# Power_Supply.net
KiCad netlist of a schematic drawn in Altium Designer
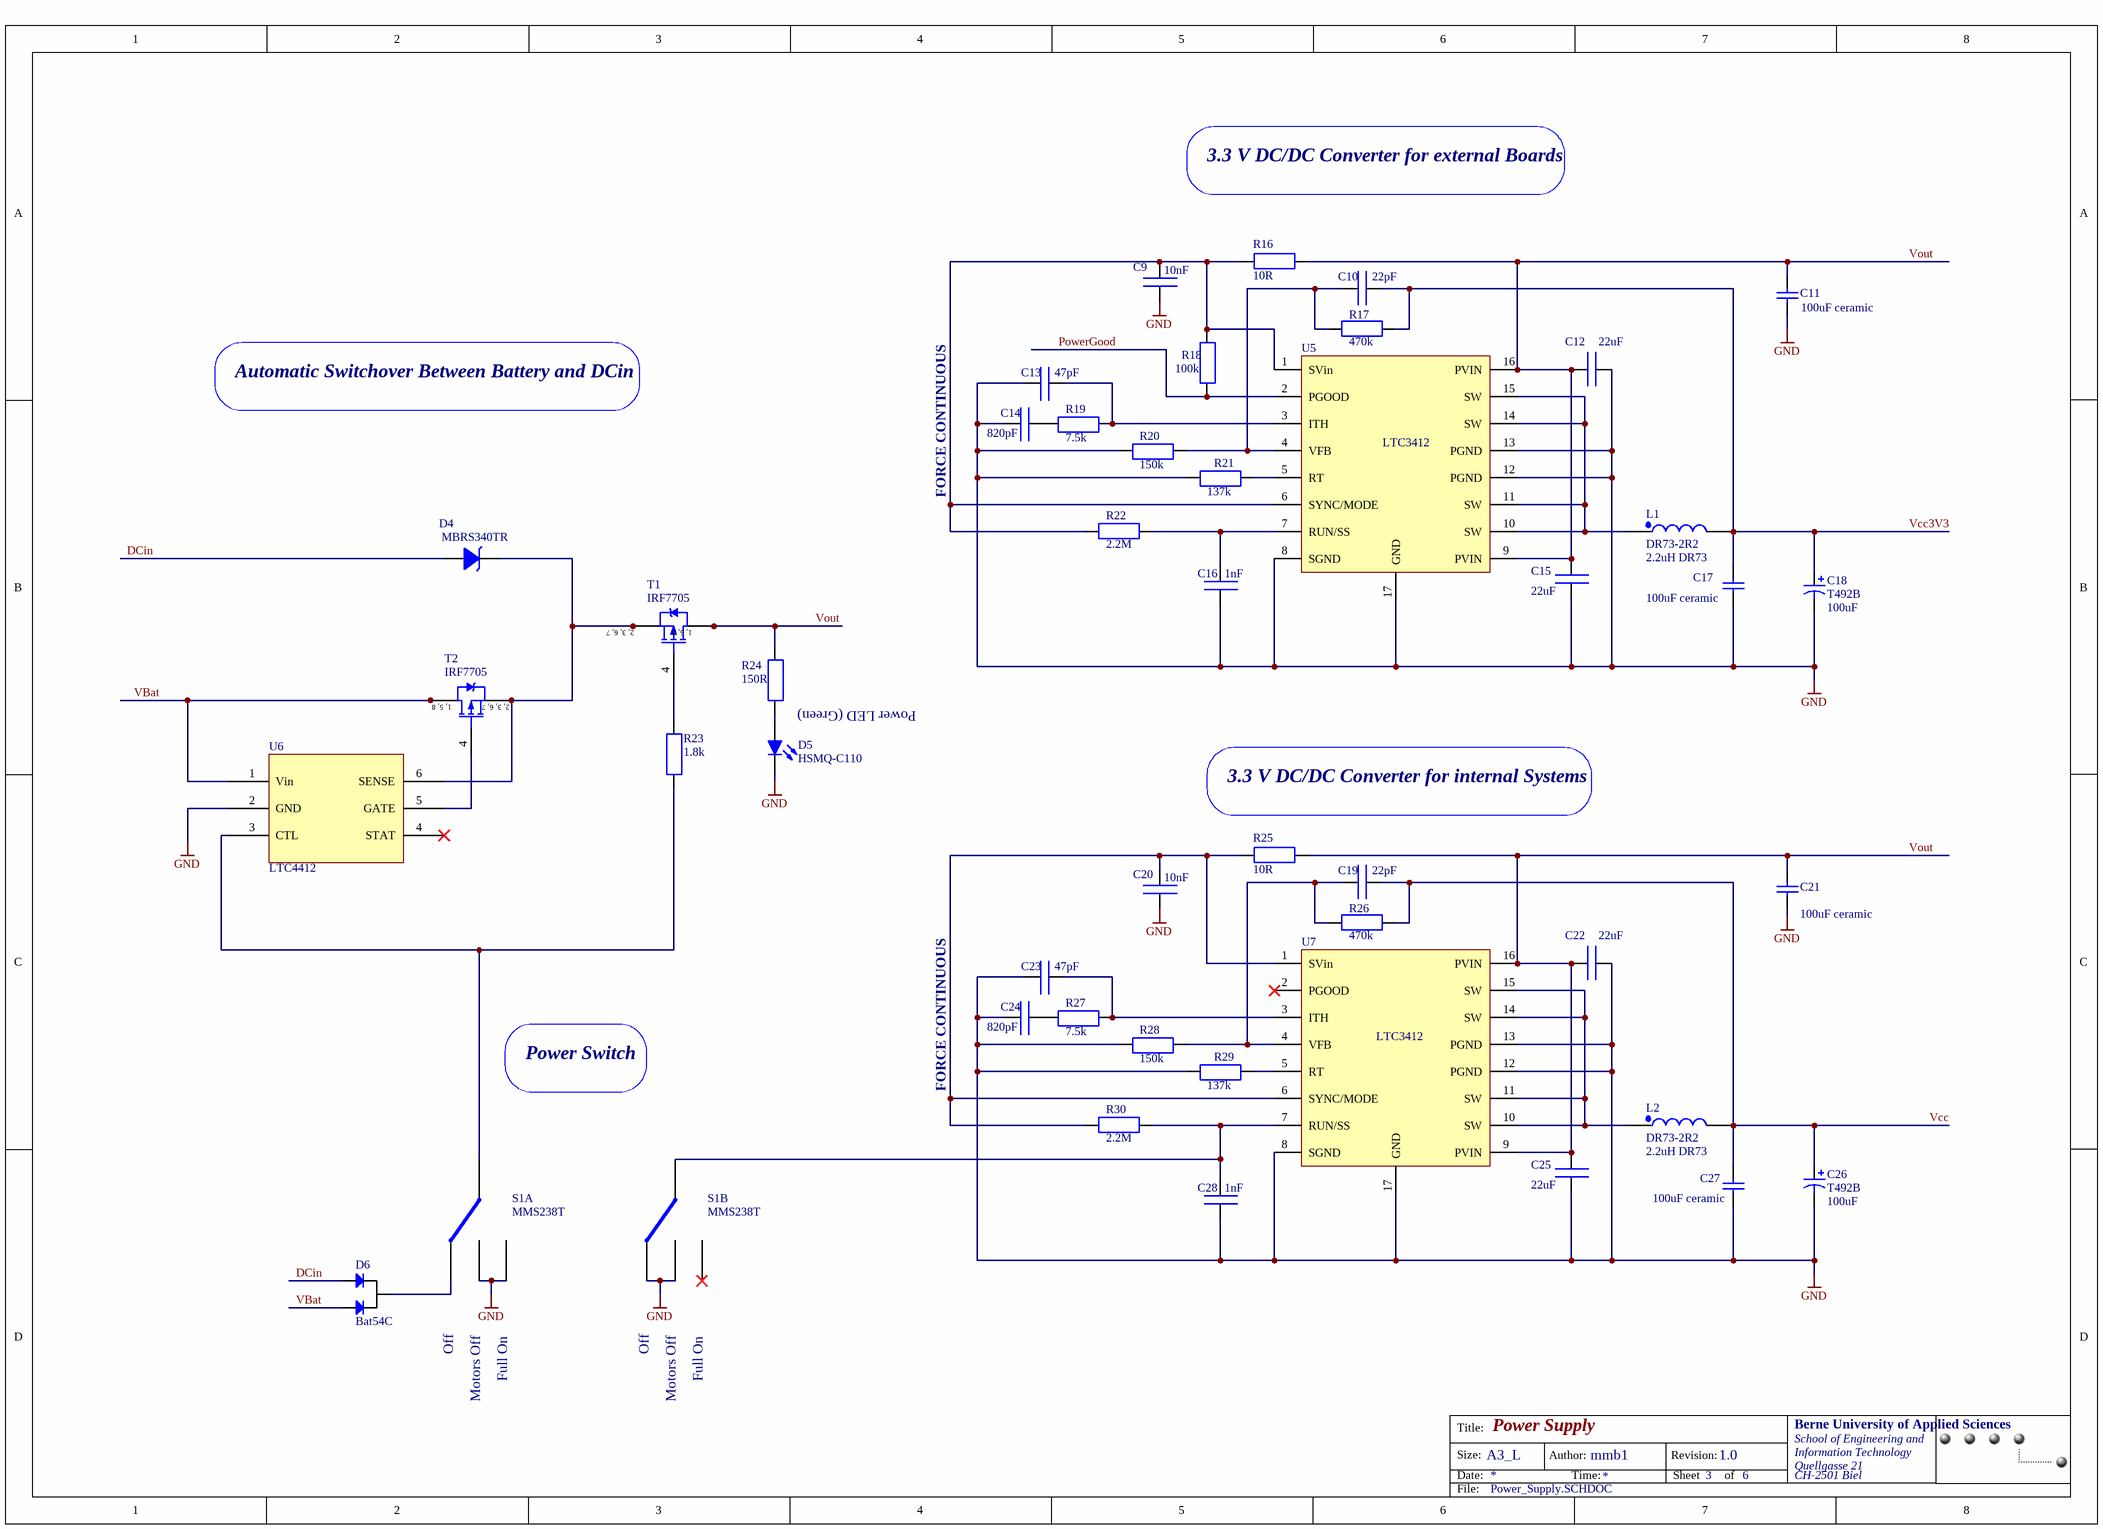
[diagram p0: Power_Supply.SCHDOC]

(export (version "E")
  (design (tool "Eeschema 10.0.6"))
  (components
    (comp (ref "C9")
      (value "10nF")
      (footprint "1608[0603]")
      (description "Capacitor")
      (fields
        (field (name "PART TYPE") "10nF")
        (field (name "MANUFACTURER") "AVX")
        (field (name "PART NUMBER") "06035C103KAT2A")
      )
      (libsource (lib "POWER_SUPPLY") (part "CAP"))
    )
    (comp (ref "C10")
      (value "22pF")
      (footprint "1608[0603]")
      (description "Capacitor")
      (fields
        (field (name "PART TYPE") "22pF")
        (field (name "MANUFACTURER") "Epcos")
        (field (name "PART NUMBER") "B37930K5220J60")
      )
      (libsource (lib "POWER_SUPPLY") (part "CAP"))
    )
    (comp (ref "C11")
      (value "100uF ceramic")
      (footprint "C1210")
      (description "Capacitor (Semiconductor SIM Model)")
      (fields
        (field (name "MANUFACTURER") "Kemet")
        (field (name "PART NUMBER") "C1210C107M9PAC7800")
        (field (name "PUBLISHER") "Altium Limited")
      )
      (libsource (lib "Miscellaneous Devices") (part "Cap Semi"))
    )
    (comp (ref "C12")
      (value "22uF")
      (footprint "C0805")
      (description "Capacitor")
      (fields (field (name "MANUFACTURER") "Kemet") (field (name "PART NUMBER") "C0805C226M9PAC7800"))
      (libsource (lib "POWER_SUPPLY") (part "CAP"))
    )
    (comp (ref "C13")
      (value "47pF")
      (footprint "1608[0603]")
      (description "Capacitor")
      (fields
        (field (name "PART TYPE") "47pF")
        (field (name "MANUFACTURER") "Murata")
        (field (name "PART NUMBER") "GRM1885C1H470JA01D")
      )
      (libsource (lib "POWER_SUPPLY") (part "CAP"))
    )
    (comp (ref "C14")
      (value "820pF")
      (footprint "1608[0603]")
      (description "Capacitor")
      (fields
        (field (name "PART TYPE") "820pF")
        (field (name "MANUFACTURER") "PHYCOMP")
        (field (name "PART NUMBER") "2238 861 15821")
      )
      (libsource (lib "POWER_SUPPLY") (part "CAP"))
    )
    (comp (ref "C15")
      (value "22uF")
      (footprint "C0805")
      (description "Capacitor")
      (fields (field (name "MANUFACTURER") "Kemet") (field (name "PART NUMBER") "C0805C226M9PAC7800"))
      (libsource (lib "POWER_SUPPLY") (part "CAP"))
    )
    (comp (ref "C16")
      (value "1nF")
      (footprint "1608[0603]")
      (description "Capacitor")
      (fields
        (field (name "PART TYPE") "1nF")
        (field (name "MANUFACTURER") "Murata")
        (field (name "PART NUMBER") "GRM188R71H102KA01D")
      )
      (libsource (lib "POWER_SUPPLY") (part "CAP"))
    )
    (comp (ref "C17")
      (value "100uF ceramic")
      (footprint "C1210")
      (description "Capacitor (Semiconductor SIM Model)")
      (fields
        (field (name "MANUFACTURER") "Kemet")
        (field (name "PART NUMBER") "C1210C107M9PAC7800")
        (field (name "PUBLISHER") "Altium Limited")
      )
      (libsource (lib "Miscellaneous Devices") (part "Cap Semi"))
    )
    (comp (ref "C18")
      (value "T492B")
      (footprint "B")
      (description "Solid Tantalum Chip Capacitor, T492 Series - CWR11 Style Per Mil-PRF-55365/8")
      (fields
        (field (name "ALTIUM_VALUE") "100uF")
        (field (name "MANUFACTURER") "AVX")
        (field (name "PART NUMBER") "TCJB107M004R0070")
        (field (name "PUBLISHER") "Altium Limited")
      )
      (libsource (lib "KEMET Chip Capacitor") (part "T492B"))
    )
    (comp (ref "C19")
      (value "22pF")
      (footprint "1608[0603]")
      (description "Capacitor")
      (fields
        (field (name "PART TYPE") "22pF")
        (field (name "MANUFACTURER") "Epcos")
        (field (name "PART NUMBER") "B37930K5220J60")
      )
      (libsource (lib "POWER_SUPPLY") (part "CAP"))
    )
    (comp (ref "C20")
      (value "10nF")
      (footprint "1608[0603]")
      (description "Capacitor")
      (fields
        (field (name "PART TYPE") "10nF")
        (field (name "MANUFACTURER") "AVX")
        (field (name "PART NUMBER") "06035C103KAT2A")
      )
      (libsource (lib "POWER_SUPPLY") (part "CAP"))
    )
    (comp (ref "C21")
      (value "100uF ceramic")
      (footprint "C1210")
      (description "Capacitor (Semiconductor SIM Model)")
      (fields
        (field (name "MANUFACTURER") "Kemet")
        (field (name "PART NUMBER") "C1210C107M9PAC7800")
        (field (name "PUBLISHER") "Altium Limited")
      )
      (libsource (lib "Miscellaneous Devices") (part "Cap Semi"))
    )
    (comp (ref "C22")
      (value "22uF")
      (footprint "C0805")
      (description "Capacitor")
      (fields (field (name "MANUFACTURER") "Kemet") (field (name "PART NUMBER") "C0805C226M9PAC7800"))
      (libsource (lib "POWER_SUPPLY") (part "CAP"))
    )
    (comp (ref "C23")
      (value "47pF")
      (footprint "1608[0603]")
      (description "Capacitor")
      (fields
        (field (name "PART TYPE") "47pF")
        (field (name "MANUFACTURER") "Murata")
        (field (name "PART NUMBER") "GRM1885C1H470JA01D")
      )
      (libsource (lib "POWER_SUPPLY") (part "CAP"))
    )
    (comp (ref "C24")
      (value "820pF")
      (footprint "1608[0603]")
      (description "Capacitor")
      (fields
        (field (name "PART TYPE") "820pF")
        (field (name "MANUFACTURER") "PHYCOMP")
        (field (name "PART NUMBER") "2238 861 15821")
      )
      (libsource (lib "POWER_SUPPLY") (part "CAP"))
    )
    (comp (ref "C25")
      (value "22uF")
      (footprint "C0805")
      (description "Capacitor")
      (fields (field (name "MANUFACTURER") "Kemet") (field (name "PART NUMBER") "C0805C226M9PAC7800"))
      (libsource (lib "POWER_SUPPLY") (part "CAP"))
    )
    (comp (ref "C26")
      (value "T492B")
      (footprint "B")
      (description "Solid Tantalum Chip Capacitor, T492 Series - CWR11 Style Per Mil-PRF-55365/8")
      (fields
        (field (name "ALTIUM_VALUE") "100uF")
        (field (name "MANUFACTURER") "AVX")
        (field (name "PART NUMBER") "TCJB107M004R0070")
        (field (name "PUBLISHER") "Altium Limited")
      )
      (libsource (lib "KEMET Chip Capacitor") (part "T492B"))
    )
    (comp (ref "C27")
      (value "100uF ceramic")
      (footprint "C1210")
      (description "Capacitor (Semiconductor SIM Model)")
      (fields
        (field (name "MANUFACTURER") "Kemet")
        (field (name "PART NUMBER") "C1210C107M9PAC7800")
        (field (name "PUBLISHER") "Altium Limited")
      )
      (libsource (lib "Miscellaneous Devices") (part "Cap Semi"))
    )
    (comp (ref "C28")
      (value "1nF")
      (footprint "1608[0603]")
      (description "Capacitor")
      (fields
        (field (name "PART TYPE") "1nF")
        (field (name "MANUFACTURER") "Murata")
        (field (name "PART NUMBER") "GRM188R71H102KA01D")
      )
      (libsource (lib "POWER_SUPPLY") (part "CAP"))
    )
    (comp (ref "D4")
      (value "MBRS340TR")
      (footprint "MBRS340")
      (fields
        (field (name "MANUFACTURER") "Vishay")
        (field (name "PART NUMBER") "MBRS340TRPBF")
        (field (name "Comment") "Schottky  Power Rectifier")
      )
      (libsource (lib "Power_supply") (part "shottky-mbrs340tr"))
    )
    (comp (ref "D5")
      (value "HSMQ-C110")
      (footprint "HSMC-C110")
      (description "LED")
      (fields (field (name "PART TYPE") "HSMQ-C110") (field (name "MANUFACTURER") "Avago"))
      (libsource (lib "Power_supply") (part "LED-HSM*-C110"))
    )
    (comp (ref "D6")
      (value "Bat54C")
      (footprint "BAT54C")
      (fields
        (field (name "PART TYPE") "Bat54C")
        (field (name "MANUFACTURER") "ST")
        (field (name "PART NUMBER") "BAT54CFILM")
      )
      (libsource (lib "Power_supply") (part "BAT54C"))
    )
    (comp (ref "L1")
      (value "2.2uH DR73")
      (footprint "B82472G4222M")
      (description "DR Series Coils from Coiltronics")
      (fields
        (field (name "PART TYPE") "DR73-2R2")
        (field (name "MANUFACTURER") "Cooper Bussmann")
        (field (name "PART NUMBER") "DR73-2R2")
      )
      (libsource (lib "Power_supply") (part "COIL-DR-SERIE"))
    )
    (comp (ref "L2")
      (value "2.2uH DR73")
      (footprint "B82472G4222M")
      (description "DR Series Coils from Coiltronics")
      (fields
        (field (name "PART TYPE") "DR73-2R2")
        (field (name "MANUFACTURER") "Cooper Bussmann")
        (field (name "PART NUMBER") "DR73-2R2")
      )
      (libsource (lib "Power_supply") (part "COIL-DR-SERIE"))
    )
    (comp (ref "R16")
      (value "10R")
      (footprint "1608[0603]")
      (description "Resistance")
      (fields
        (field (name "PART TYPE") "10R")
        (field (name "MANUFACTURER") "Multicomp")
        (field (name "PART NUMBER") "MC 0.063W 0603 1% 10R")
      )
      (libsource (lib "POWER_SUPPLY") (part "RES"))
    )
    (comp (ref "R17")
      (value "470k")
      (footprint "1608[0603]")
      (description "Resistance")
      (fields
        (field (name "PART TYPE") "470k")
        (field (name "MANUFACTURER") "Multicomp")
        (field (name "PART NUMBER") "MC 0.063W 0603 1% 470K")
      )
      (libsource (lib "POWER_SUPPLY") (part "RES"))
    )
    (comp (ref "R18")
      (value "100k")
      (footprint "1608[0603]")
      (description "Resistance")
      (fields
        (field (name "PART TYPE") "100k")
        (field (name "MANUFACTURER") "Multicomp")
        (field (name "PART NUMBER") "MC 0.063W 0603 1% 100K")
      )
      (libsource (lib "POWER_SUPPLY") (part "RES"))
    )
    (comp (ref "R19")
      (value "7.5k")
      (footprint "1608[0603]")
      (description "Resistance")
      (fields
        (field (name "PART TYPE") "7.5k")
        (field (name "MANUFACTURER") "Multicomp")
        (field (name "PART NUMBER") "MC 0.063W 0603 1% 7K5")
      )
      (libsource (lib "POWER_SUPPLY") (part "RES"))
    )
    (comp (ref "R20")
      (value "150k")
      (footprint "1608[0603]")
      (description "Resistance")
      (fields
        (field (name "PART TYPE") "150k")
        (field (name "MANUFACTURER") "Multicomp")
        (field (name "PART NUMBER") "MC 0.063W 0603 1% 150K")
      )
      (libsource (lib "POWER_SUPPLY") (part "RES"))
    )
    (comp (ref "R21")
      (value "137k")
      (footprint "1608[0603]")
      (description "Resistance")
      (fields
        (field (name "PART TYPE") "137k")
        (field (name "MANUFACTURER") "Multicomp")
        (field (name "PART NUMBER") "MC 0.063W 0603 1% 137K")
      )
      (libsource (lib "POWER_SUPPLY") (part "RES"))
    )
    (comp (ref "R22")
      (value "2.2M")
      (footprint "1608[0603]")
      (description "Resistance")
      (fields
        (field (name "PART TYPE") "2.2M")
        (field (name "MANUFACTURER") "PHYCOMP")
        (field (name "PART NUMBER") "232270462205")
      )
      (libsource (lib "POWER_SUPPLY") (part "RES"))
    )
    (comp (ref "R23")
      (value "1.8k")
      (footprint "1608[0603]")
      (description "Resistance")
      (fields
        (field (name "PART TYPE") "1.8k")
        (field (name "MANUFACTURER") "Multicomp")
        (field (name "PART NUMBER") "MC 0.063W 0603 1% 1K8")
      )
      (libsource (lib "POWER_SUPPLY") (part "RES"))
    )
    (comp (ref "R24")
      (value "150R")
      (footprint "1608[0603]")
      (description "Resistance")
      (fields
        (field (name "PART TYPE") "150R")
        (field (name "MANUFACTURER") "Multicomp")
        (field (name "PART NUMBER") "MC 0.063W 0603 1% 150R")
      )
      (libsource (lib "POWER_SUPPLY") (part "RES"))
    )
    (comp (ref "R25")
      (value "10R")
      (footprint "1608[0603]")
      (description "Resistance")
      (fields
        (field (name "PART TYPE") "10R")
        (field (name "MANUFACTURER") "Multicomp")
        (field (name "PART NUMBER") "MC 0.063W 0603 1% 10R")
      )
      (libsource (lib "POWER_SUPPLY") (part "RES"))
    )
    (comp (ref "R26")
      (value "470k")
      (footprint "1608[0603]")
      (description "Resistance")
      (fields
        (field (name "PART TYPE") "470k")
        (field (name "MANUFACTURER") "Multicomp")
        (field (name "PART NUMBER") "MC 0.063W 0603 1% 470K")
      )
      (libsource (lib "POWER_SUPPLY") (part "RES"))
    )
    (comp (ref "R27")
      (value "7.5k")
      (footprint "1608[0603]")
      (description "Resistance")
      (fields
        (field (name "PART TYPE") "7.5k")
        (field (name "MANUFACTURER") "Multicomp")
        (field (name "PART NUMBER") "MC 0.063W 0603 1% 7K5")
      )
      (libsource (lib "POWER_SUPPLY") (part "RES"))
    )
    (comp (ref "R28")
      (value "150k")
      (footprint "1608[0603]")
      (description "Resistance")
      (fields
        (field (name "PART TYPE") "150k")
        (field (name "MANUFACTURER") "Multicomp")
        (field (name "PART NUMBER") "MC 0.063W 0603 1% 150K")
      )
      (libsource (lib "POWER_SUPPLY") (part "RES"))
    )
    (comp (ref "R29")
      (value "137k")
      (footprint "1608[0603]")
      (description "Resistance")
      (fields
        (field (name "PART TYPE") "137k")
        (field (name "MANUFACTURER") "Multicomp")
        (field (name "PART NUMBER") "MC 0.063W 0603 1% 137K")
      )
      (libsource (lib "POWER_SUPPLY") (part "RES"))
    )
    (comp (ref "R30")
      (value "2.2M")
      (footprint "1608[0603]")
      (description "Resistance")
      (fields
        (field (name "PART TYPE") "2.2M")
        (field (name "MANUFACTURER") "PHYCOMP")
        (field (name "PART NUMBER") "232270462205")
      )
      (libsource (lib "POWER_SUPPLY") (part "RES"))
    )
    (comp (ref "S1")
      (value "MMS238T")
      (footprint "switch_mms238t")
      (fields
        (field (name "PART TYPE") "MMS238T")
        (field (name "MANUFACTURER") "KNITTER")
        (field (name "PART NUMBER") "MMS 238 T")
      )
      (libsource (lib "Power_supply") (part "switch-mms238T"))
    )
    (comp (ref "T1")
      (value "IRF7705")
      (footprint "TSSOP-8")
      (description "HEXFET Power MOSFET")
      (fields
        (field (name "MANUFACTURER") "IRF")
        (field (name "PART NUMBER") "IRF7705TRPBF")
        (field (name "PUBLISHER") "Altium Limited")
      )
      (libsource (lib "IR Discrete MOSFET - Power") (part "IRF7705"))
    )
    (comp (ref "T2")
      (value "IRF7705")
      (footprint "TSSOP-8")
      (description "HEXFET Power MOSFET")
      (fields
        (field (name "MANUFACTURER") "IRF")
        (field (name "PART NUMBER") "IRF7705TRPBF")
        (field (name "PUBLISHER") "Altium Limited")
      )
      (libsource (lib "IR Discrete MOSFET - Power") (part "IRF7705"))
    )
    (comp (ref "U5")
      (value "LTC3412")
      (footprint "LCT3412A_New")
      (fields (field (name "MANUFACTURER") "Linear") (field (name "PART NUMBER") "LTC3412AEFE#PBF"))
      (libsource (lib "Power_supply_library") (part "LTC3412A_NEW"))
    )
    (comp (ref "U6")
      (value "LTC4412")
      (footprint "MAX5467")
      (fields (field (name "MANUFACTURER") "Linear") (field (name "PART NUMBER") "LTC4412ES6#PBF"))
      (libsource (lib "Power_supply_library") (part "LTC4412"))
    )
    (comp (ref "U7")
      (value "LTC3412")
      (footprint "LCT3412A_New")
      (fields (field (name "MANUFACTURER") "Linear") (field (name "PART NUMBER") "LTC3412AEFE#PBF"))
      (libsource (lib "Power_supply_library") (part "LTC3412A_NEW"))
    )
  )
  (nets
    (net (code "1") (name "/DCin") (class "Default")
      (node (ref "D4") (pin "1") (pinfunction "Anode_1") (pintype "passive"))
      (node (ref "D6") (pin "2") (pinfunction "A_2") (pintype "passive"))
    )
    (net (code "2") (name "/PowerGood") (class "Default")
      (node (ref "R18") (pin "1") (pinfunction "J1_1") (pintype "passive"))
      (node (ref "U5") (pin "2") (pinfunction "PGOOD_2") (pintype "passive"))
    )
    (net (code "3") (name "/VBat") (class "Default")
      (node (ref "D6") (pin "1") (pinfunction "A_1") (pintype "passive"))
      (node (ref "T2") (pin "1") (pinfunction "D_1") (pintype "passive"))
      (node (ref "T2") (pin "5") (pinfunction "D_5") (pintype "passive"))
      (node (ref "T2") (pin "8") (pinfunction "D_8") (pintype "passive"))
      (node (ref "U6") (pin "1") (pinfunction "Vin_1") (pintype "passive"))
    )
    (net (code "4") (name "/Vcc") (class "Default")
      (node (ref "C19") (pin "1") (pinfunction "J1_1") (pintype "passive"))
      (node (ref "C26") (pin "1") (pinfunction "1_1") (pintype "passive"))
      (node (ref "C27") (pin "2") (pinfunction "2_2") (pintype "passive"))
      (node (ref "L2") (pin "2") (pinfunction "2_2") (pintype "passive"))
      (node (ref "R26") (pin "1") (pinfunction "J1_1") (pintype "passive"))
    )
    (net (code "5") (name "/Vcc3V3") (class "Default")
      (node (ref "C10") (pin "1") (pinfunction "J1_1") (pintype "passive"))
      (node (ref "C17") (pin "2") (pinfunction "2_2") (pintype "passive"))
      (node (ref "C18") (pin "1") (pinfunction "1_1") (pintype "passive"))
      (node (ref "L1") (pin "2") (pinfunction "2_2") (pintype "passive"))
      (node (ref "R17") (pin "1") (pinfunction "J1_1") (pintype "passive"))
    )
    (net (code "6") (name "/Vout") (class "Default")
      (node (ref "C11") (pin "2") (pinfunction "2_2") (pintype "passive"))
      (node (ref "C12") (pin "2") (pinfunction "J2_2") (pintype "passive"))
      (node (ref "C15") (pin "2") (pinfunction "J2_2") (pintype "passive"))
      (node (ref "C21") (pin "2") (pinfunction "2_2") (pintype "passive"))
      (node (ref "C22") (pin "2") (pinfunction "J2_2") (pintype "passive"))
      (node (ref "C25") (pin "2") (pinfunction "J2_2") (pintype "passive"))
      (node (ref "R16") (pin "1") (pinfunction "J1_1") (pintype "passive"))
      (node (ref "R24") (pin "2") (pinfunction "J2_2") (pintype "passive"))
      (node (ref "R25") (pin "1") (pinfunction "J1_1") (pintype "passive"))
      (node (ref "T1") (pin "1") (pinfunction "D_1") (pintype "passive"))
      (node (ref "T1") (pin "5") (pinfunction "D_5") (pintype "passive"))
      (node (ref "T1") (pin "8") (pinfunction "D_8") (pintype "passive"))
      (node (ref "U5") (pin "16") (pinfunction "PVIN_16") (pintype "passive"))
      (node (ref "U5") (pin "9") (pinfunction "PVIN_9") (pintype "passive"))
      (node (ref "U7") (pin "16") (pinfunction "PVIN_16") (pintype "passive"))
      (node (ref "U7") (pin "9") (pinfunction "PVIN_9") (pintype "passive"))
    )
    (net (code "7") (name "GND") (class "Default")
      (node (ref "C11") (pin "1") (pinfunction "1_1") (pintype "passive"))
      (node (ref "C12") (pin "1") (pinfunction "J1_1") (pintype "passive"))
      (node (ref "C13") (pin "1") (pinfunction "J1_1") (pintype "passive"))
      (node (ref "C14") (pin "1") (pinfunction "J1_1") (pintype "passive"))
      (node (ref "C15") (pin "1") (pinfunction "J1_1") (pintype "passive"))
      (node (ref "C16") (pin "1") (pinfunction "J1_1") (pintype "passive"))
      (node (ref "C17") (pin "1") (pinfunction "1_1") (pintype "passive"))
      (node (ref "C18") (pin "2") (pinfunction "2_2") (pintype "passive"))
      (node (ref "C20") (pin "1") (pinfunction "J1_1") (pintype "passive"))
      (node (ref "C21") (pin "1") (pinfunction "1_1") (pintype "passive"))
      (node (ref "C22") (pin "1") (pinfunction "J1_1") (pintype "passive"))
      (node (ref "C23") (pin "1") (pinfunction "J1_1") (pintype "passive"))
      (node (ref "C24") (pin "1") (pinfunction "J1_1") (pintype "passive"))
      (node (ref "C25") (pin "1") (pinfunction "J1_1") (pintype "passive"))
      (node (ref "C26") (pin "2") (pinfunction "2_2") (pintype "passive"))
      (node (ref "C27") (pin "1") (pinfunction "1_1") (pintype "passive"))
      (node (ref "C28") (pin "1") (pinfunction "J1_1") (pintype "passive"))
      (node (ref "C9") (pin "1") (pinfunction "J1_1") (pintype "passive"))
      (node (ref "D5") (pin "1") (pinfunction "K_1") (pintype "passive"))
      (node (ref "R20") (pin "1") (pinfunction "J1_1") (pintype "passive"))
      (node (ref "R21") (pin "1") (pinfunction "J1_1") (pintype "passive"))
      (node (ref "R28") (pin "1") (pinfunction "J1_1") (pintype "passive"))
      (node (ref "R29") (pin "1") (pinfunction "J1_1") (pintype "passive"))
      (node (ref "S1") (pin "3") (pintype "passive"))
      (node (ref "S1") (pin "4") (pintype "passive"))
      (node (ref "S1") (pin "6") (pintype "passive"))
      (node (ref "S1") (pin "8") (pintype "passive"))
      (node (ref "U5") (pin "12") (pinfunction "PGND_12") (pintype "passive"))
      (node (ref "U5") (pin "13") (pinfunction "PGND_13") (pintype "passive"))
      (node (ref "U5") (pin "17") (pinfunction "GND_17") (pintype "passive"))
      (node (ref "U5") (pin "8") (pinfunction "SGND_8") (pintype "passive"))
      (node (ref "U6") (pin "2") (pinfunction "GND_2") (pintype "passive"))
      (node (ref "U7") (pin "12") (pinfunction "PGND_12") (pintype "passive"))
      (node (ref "U7") (pin "13") (pinfunction "PGND_13") (pintype "passive"))
      (node (ref "U7") (pin "17") (pinfunction "GND_17") (pintype "passive"))
      (node (ref "U7") (pin "8") (pinfunction "SGND_8") (pintype "passive"))
    )
    (net (code "8") (name "Net-(C9-J2)") (class "Default")
      (node (ref "C9") (pin "2") (pinfunction "J2_2") (pintype "passive"))
      (node (ref "R16") (pin "2") (pinfunction "J2_2") (pintype "passive"))
      (node (ref "R18") (pin "2") (pinfunction "J2_2") (pintype "passive"))
      (node (ref "R22") (pin "2") (pinfunction "J2_2") (pintype "passive"))
      (node (ref "U5") (pin "1") (pinfunction "SVin_1") (pintype "passive"))
      (node (ref "U5") (pin "6") (pinfunction "SYNC/MODE_6") (pintype "passive"))
    )
    (net (code "9") (name "Net-(C10-J2)") (class "Default")
      (node (ref "C10") (pin "2") (pinfunction "J2_2") (pintype "passive"))
      (node (ref "R17") (pin "2") (pinfunction "J2_2") (pintype "passive"))
      (node (ref "R20") (pin "2") (pinfunction "J2_2") (pintype "passive"))
      (node (ref "U5") (pin "4") (pinfunction "VFB_4") (pintype "passive"))
    )
    (net (code "10") (name "Net-(C13-J2)") (class "Default")
      (node (ref "C13") (pin "2") (pinfunction "J2_2") (pintype "passive"))
      (node (ref "R19") (pin "2") (pinfunction "J2_2") (pintype "passive"))
      (node (ref "U5") (pin "3") (pinfunction "ITH_3") (pintype "passive"))
    )
    (net (code "11") (name "Net-(C14-J2)") (class "Default")
      (node (ref "C14") (pin "2") (pinfunction "J2_2") (pintype "passive"))
      (node (ref "R19") (pin "1") (pinfunction "J1_1") (pintype "passive"))
    )
    (net (code "12") (name "Net-(C16-J2)") (class "Default")
      (node (ref "C16") (pin "2") (pinfunction "J2_2") (pintype "passive"))
      (node (ref "R22") (pin "1") (pinfunction "J1_1") (pintype "passive"))
      (node (ref "U5") (pin "7") (pinfunction "RUN/SS_7") (pintype "passive"))
    )
    (net (code "13") (name "Net-(C19-J2)") (class "Default")
      (node (ref "C19") (pin "2") (pinfunction "J2_2") (pintype "passive"))
      (node (ref "R26") (pin "2") (pinfunction "J2_2") (pintype "passive"))
      (node (ref "R28") (pin "2") (pinfunction "J2_2") (pintype "passive"))
      (node (ref "U7") (pin "4") (pinfunction "VFB_4") (pintype "passive"))
    )
    (net (code "14") (name "Net-(C20-J2)") (class "Default")
      (node (ref "C20") (pin "2") (pinfunction "J2_2") (pintype "passive"))
      (node (ref "R25") (pin "2") (pinfunction "J2_2") (pintype "passive"))
      (node (ref "R30") (pin "2") (pinfunction "J2_2") (pintype "passive"))
      (node (ref "U7") (pin "1") (pinfunction "SVin_1") (pintype "passive"))
      (node (ref "U7") (pin "6") (pinfunction "SYNC/MODE_6") (pintype "passive"))
    )
    (net (code "15") (name "Net-(C23-J2)") (class "Default")
      (node (ref "C23") (pin "2") (pinfunction "J2_2") (pintype "passive"))
      (node (ref "R27") (pin "2") (pinfunction "J2_2") (pintype "passive"))
      (node (ref "U7") (pin "3") (pinfunction "ITH_3") (pintype "passive"))
    )
    (net (code "16") (name "Net-(C24-J2)") (class "Default")
      (node (ref "C24") (pin "2") (pinfunction "J2_2") (pintype "passive"))
      (node (ref "R27") (pin "1") (pinfunction "J1_1") (pintype "passive"))
    )
    (net (code "17") (name "Net-(C28-J2)") (class "Default")
      (node (ref "C28") (pin "2") (pinfunction "J2_2") (pintype "passive"))
      (node (ref "R30") (pin "1") (pinfunction "J1_1") (pintype "passive"))
      (node (ref "S1") (pin "7") (pintype "passive"))
      (node (ref "U7") (pin "7") (pinfunction "RUN/SS_7") (pintype "passive"))
    )
    (net (code "18") (name "Net-(D4-Cathode)") (class "Default")
      (node (ref "D4") (pin "2") (pinfunction "Cathode_2") (pintype "passive"))
      (node (ref "T1") (pin "2") (pinfunction "S_2") (pintype "passive"))
      (node (ref "T1") (pin "3") (pinfunction "S_3") (pintype "passive"))
      (node (ref "T1") (pin "6") (pinfunction "S_6") (pintype "passive"))
      (node (ref "T1") (pin "7") (pinfunction "S_7") (pintype "passive"))
      (node (ref "T2") (pin "2") (pinfunction "S_2") (pintype "passive"))
      (node (ref "T2") (pin "3") (pinfunction "S_3") (pintype "passive"))
      (node (ref "T2") (pin "6") (pinfunction "S_6") (pintype "passive"))
      (node (ref "T2") (pin "7") (pinfunction "S_7") (pintype "passive"))
      (node (ref "U6") (pin "6") (pinfunction "SENSE_6") (pintype "passive"))
    )
    (net (code "19") (name "Net-(D5-A)") (class "Default")
      (node (ref "D5") (pin "2") (pinfunction "A_2") (pintype "passive"))
      (node (ref "R24") (pin "1") (pinfunction "J1_1") (pintype "passive"))
    )
    (net (code "20") (name "Net-(D6-K)") (class "Default")
      (node (ref "D6") (pin "3") (pinfunction "K_3") (pintype "passive"))
      (node (ref "S1") (pin "1") (pintype "passive"))
    )
    (net (code "21") (name "Net-(L1-Pad1)") (class "Default")
      (node (ref "L1") (pin "1") (pinfunction "1_1") (pintype "passive"))
      (node (ref "U5") (pin "10") (pinfunction "SW_10") (pintype "passive"))
      (node (ref "U5") (pin "11") (pinfunction "SW_11") (pintype "passive"))
      (node (ref "U5") (pin "14") (pinfunction "SW_14") (pintype "passive"))
      (node (ref "U5") (pin "15") (pinfunction "SW_15") (pintype "passive"))
    )
    (net (code "22") (name "Net-(L2-Pad1)") (class "Default")
      (node (ref "L2") (pin "1") (pinfunction "1_1") (pintype "passive"))
      (node (ref "U7") (pin "10") (pinfunction "SW_10") (pintype "passive"))
      (node (ref "U7") (pin "11") (pinfunction "SW_11") (pintype "passive"))
      (node (ref "U7") (pin "14") (pinfunction "SW_14") (pintype "passive"))
      (node (ref "U7") (pin "15") (pinfunction "SW_15") (pintype "passive"))
    )
    (net (code "23") (name "Net-(R21-J2)") (class "Default")
      (node (ref "R21") (pin "2") (pinfunction "J2_2") (pintype "passive"))
      (node (ref "U5") (pin "5") (pinfunction "RT_5") (pintype "passive"))
    )
    (net (code "24") (name "Net-(R23-J1)") (class "Default")
      (node (ref "R23") (pin "1") (pinfunction "J1_1") (pintype "passive"))
      (node (ref "S1") (pin "2") (pintype "passive"))
      (node (ref "U6") (pin "3") (pinfunction "CTL_3") (pintype "passive"))
    )
    (net (code "25") (name "Net-(R23-J2)") (class "Default")
      (node (ref "R23") (pin "2") (pinfunction "J2_2") (pintype "passive"))
      (node (ref "T1") (pin "4") (pinfunction "G_4") (pintype "passive"))
    )
    (net (code "26") (name "Net-(R29-J2)") (class "Default")
      (node (ref "R29") (pin "2") (pinfunction "J2_2") (pintype "passive"))
      (node (ref "U7") (pin "5") (pinfunction "RT_5") (pintype "passive"))
    )
    (net (code "27") (name "Net-(T2-G)") (class "Default")
      (node (ref "T2") (pin "4") (pinfunction "G_4") (pintype "passive"))
      (node (ref "U6") (pin "5") (pinfunction "GATE_5") (pintype "passive"))
    )
    (net (code "28") (name "unconnected-(S1-Pad5)") (class "Default")
      (node (ref "S1") (pin "5") (pintype "passive+no_connect"))
    )
    (net (code "29") (name "unconnected-(U6-STAT-Pad4)") (class "Default")
      (node (ref "U6") (pin "4") (pinfunction "STAT_4") (pintype "passive+no_connect"))
    )
    (net (code "30") (name "unconnected-(U7-PGOOD-Pad2)") (class "Default")
      (node (ref "U7") (pin "2") (pinfunction "PGOOD_2") (pintype "passive+no_connect"))
    )
  )
)
